# BLDC-PWR-CONROLLER.net
KiCad netlist of a schematic drawn in Altium Designer
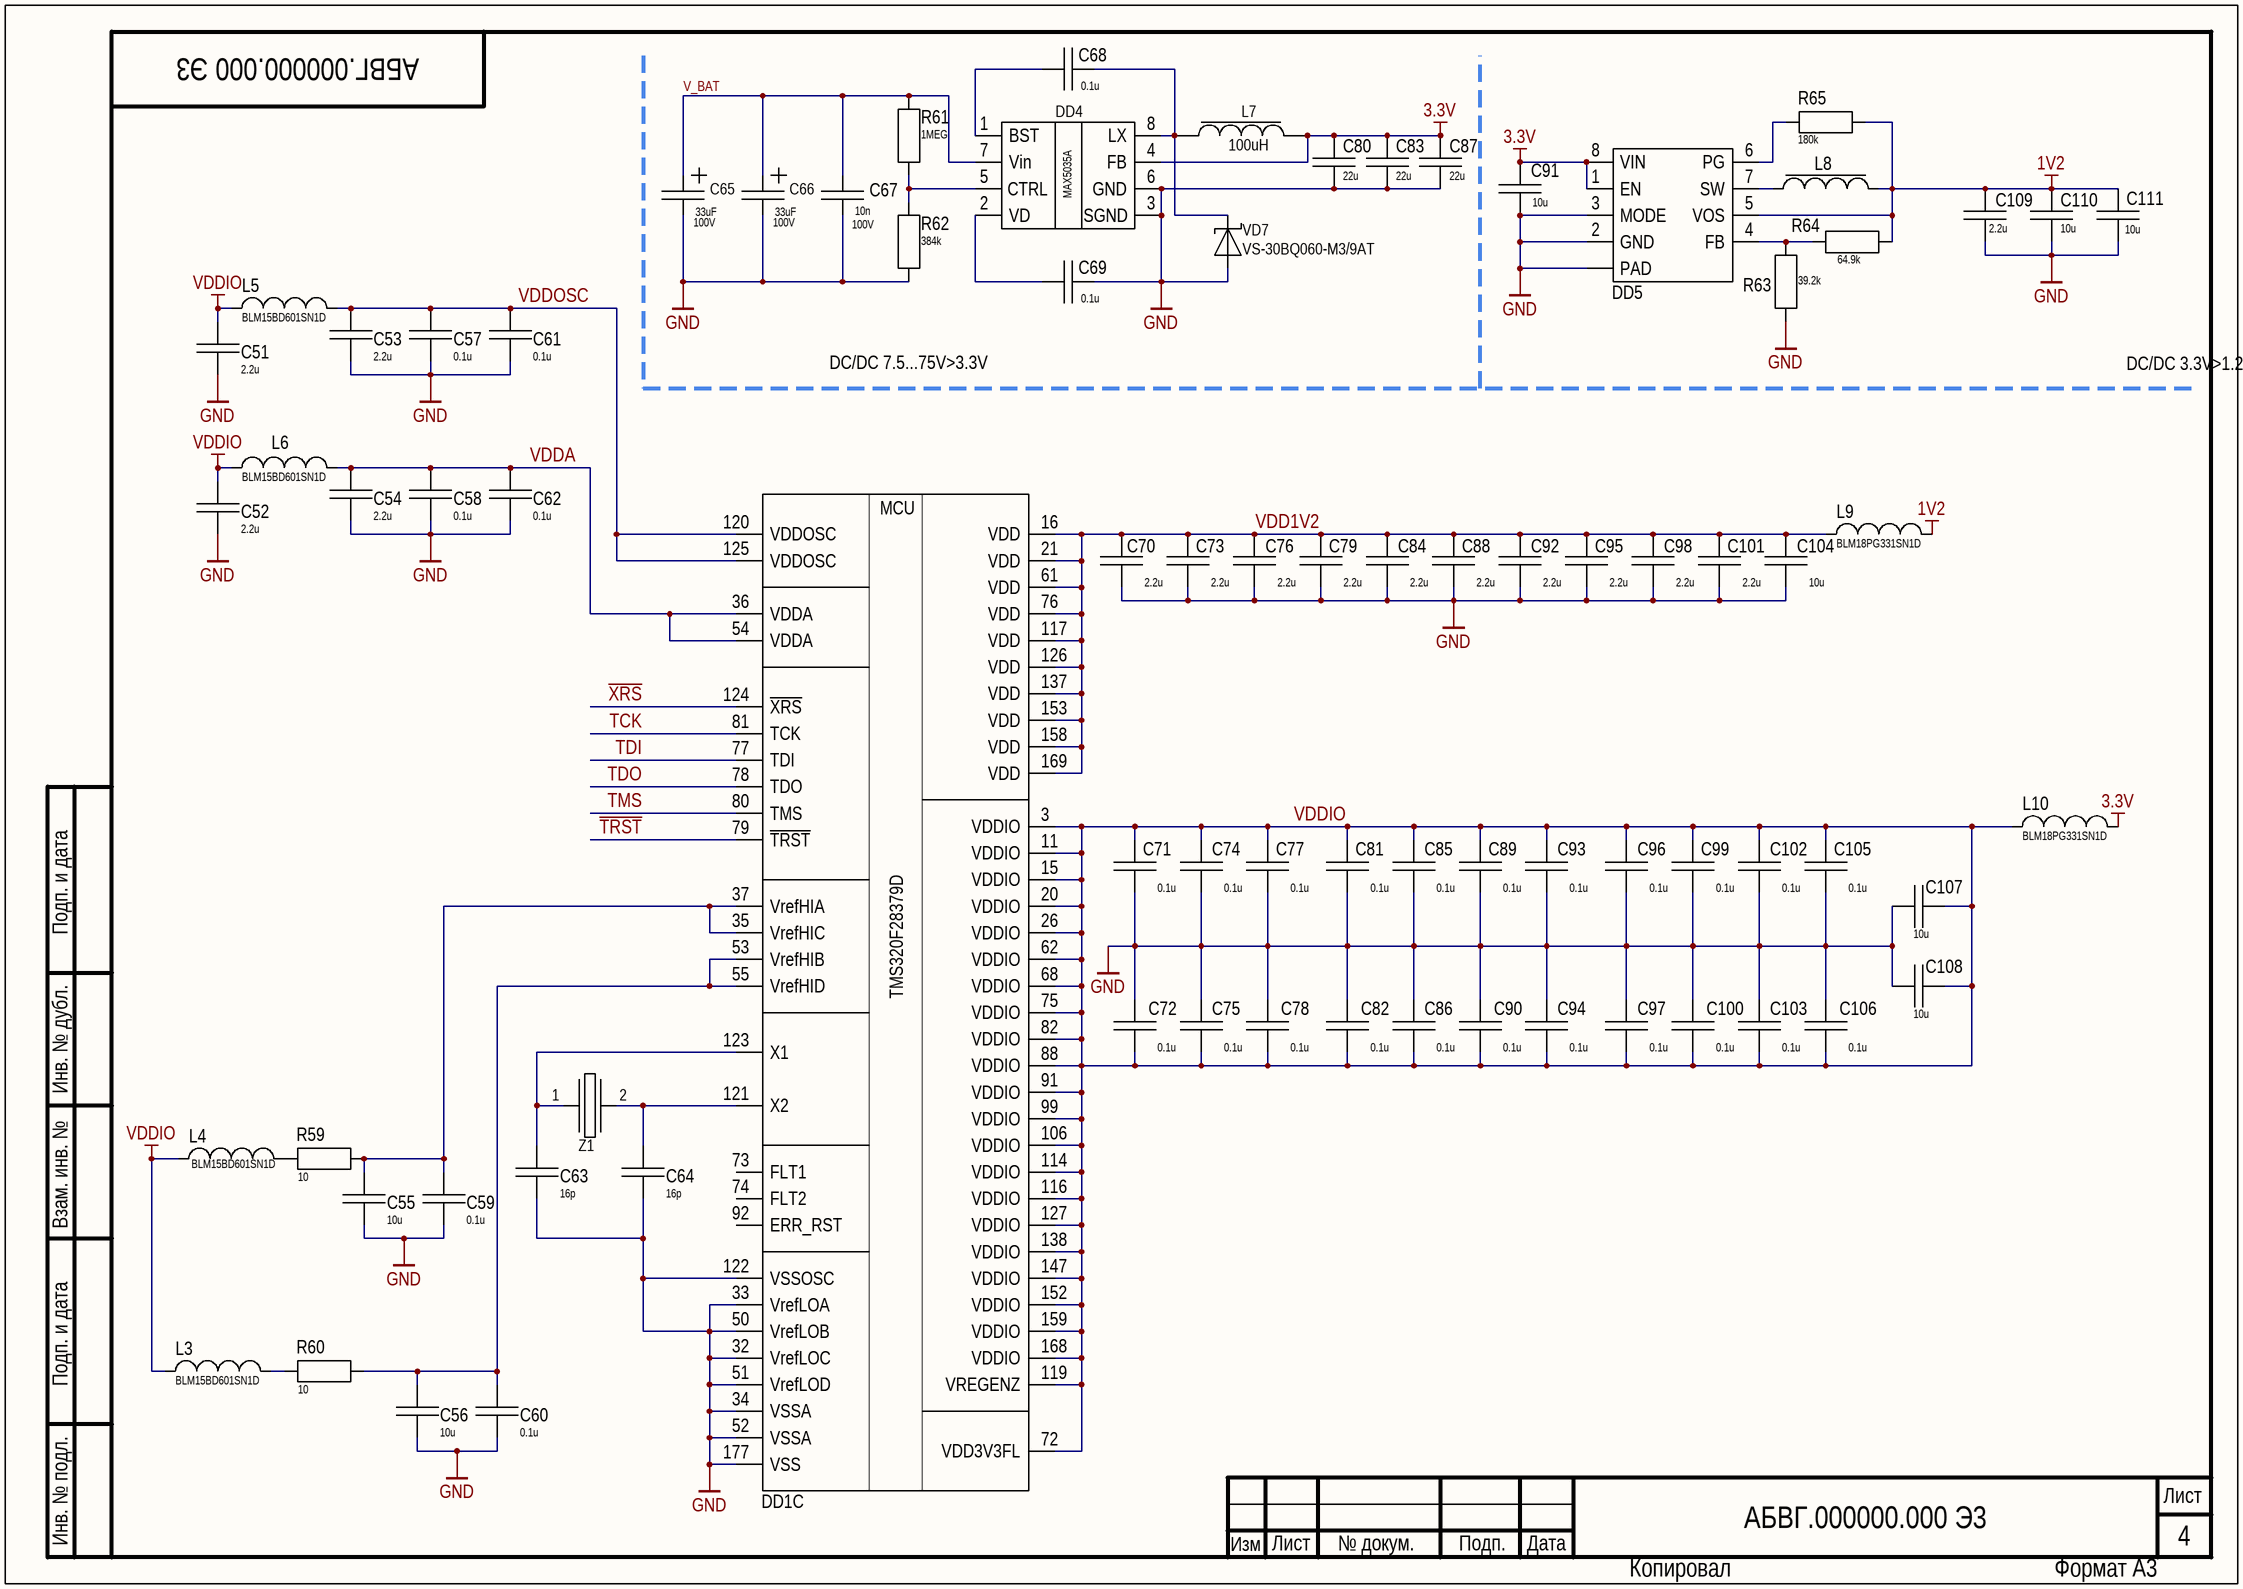
[diagram p0: BLDC-PWR-CONROLLER.SchDoc]

(export (version "E")
  (design (tool "Eeschema 10.0.6"))
  (components
    (comp (ref "C51")
      (value "2.2u")
      (footprint "CAP: 0402")
      (fields (field (name "VOLTAGE") "6.3V") (field (name "PARTNUMBER") "CC0402MRX5R5BB106"))
      (libsource (lib "Fider_Board_Lib") (part "CAP 0402"))
    )
    (comp (ref "C52")
      (value "2.2u")
      (footprint "CAP: 0402")
      (fields (field (name "VOLTAGE") "6.3V") (field (name "PARTNUMBER") "CC0402MRX5R5BB106"))
      (libsource (lib "Fider_Board_Lib") (part "CAP 0402"))
    )
    (comp (ref "C53")
      (value "2.2u")
      (footprint "CAP: 0402")
      (fields (field (name "VOLTAGE") "6.3V") (field (name "PARTNUMBER") "CC0402MRX5R5BB106"))
      (libsource (lib "Fider_Board_Lib") (part "CAP 0402"))
    )
    (comp (ref "C54")
      (value "2.2u")
      (footprint "CAP: 0402")
      (fields (field (name "VOLTAGE") "6.3V") (field (name "PARTNUMBER") "CC0402MRX5R5BB106"))
      (libsource (lib "Fider_Board_Lib") (part "CAP 0402"))
    )
    (comp (ref "C55")
      (value "10u")
      (footprint "CAP: 0402")
      (fields (field (name "VOLTAGE") "6.3V") (field (name "PARTNUMBER") "CC0402MRX5R5BB106"))
      (libsource (lib "Fider_Board_Lib") (part "CAP 0402"))
    )
    (comp (ref "C56")
      (value "10u")
      (footprint "CAP: 0402")
      (fields (field (name "VOLTAGE") "6.3V") (field (name "PARTNUMBER") "CC0402MRX5R5BB106"))
      (libsource (lib "Fider_Board_Lib") (part "CAP 0402"))
    )
    (comp (ref "C57")
      (value "0.1u")
      (footprint "CAP: 0402")
      (fields
        (field (name "VOLTAGE") "10V")
        (field (name "PARTNUMBER") "C0402C104K8PAC")
        (field (name "MANUFACTURER") "Kemet")
      )
      (libsource (lib "Fider_Board_Lib") (part "CAP 0402"))
    )
    (comp (ref "C58")
      (value "0.1u")
      (footprint "CAP: 0402")
      (fields
        (field (name "VOLTAGE") "10V")
        (field (name "PARTNUMBER") "C0402C104K8PAC")
        (field (name "MANUFACTURER") "Kemet")
      )
      (libsource (lib "Fider_Board_Lib") (part "CAP 0402"))
    )
    (comp (ref "C59")
      (value "0.1u")
      (footprint "CAP: 0402")
      (fields
        (field (name "VOLTAGE") "10V")
        (field (name "PARTNUMBER") "C0402C104K8PAC")
        (field (name "MANUFACTURER") "Kemet")
      )
      (libsource (lib "Fider_Board_Lib") (part "CAP 0402"))
    )
    (comp (ref "C60")
      (value "0.1u")
      (footprint "CAP: 0402")
      (fields
        (field (name "VOLTAGE") "10V")
        (field (name "PARTNUMBER") "C0402C104K8PAC")
        (field (name "MANUFACTURER") "Kemet")
      )
      (libsource (lib "Fider_Board_Lib") (part "CAP 0402"))
    )
    (comp (ref "C61")
      (value "0.1u")
      (footprint "CAP: 0402")
      (fields
        (field (name "VOLTAGE") "10V")
        (field (name "PARTNUMBER") "C0402C104K8PAC")
        (field (name "MANUFACTURER") "Kemet")
      )
      (libsource (lib "Fider_Board_Lib") (part "CAP 0402"))
    )
    (comp (ref "C62")
      (value "0.1u")
      (footprint "CAP: 0402")
      (fields
        (field (name "VOLTAGE") "10V")
        (field (name "PARTNUMBER") "C0402C104K8PAC")
        (field (name "MANUFACTURER") "Kemet")
      )
      (libsource (lib "Fider_Board_Lib") (part "CAP 0402"))
    )
    (comp (ref "C63")
      (value "16p")
      (footprint "CAP: 0402")
      (fields
        (field (name "VOLTAGE") "50V")
        (field (name "PARTNUMBER") "GRM1555C1H160JA01D")
        (field (name "MANUFACTURER") "Kemet")
      )
      (libsource (lib "Fider_Board_Lib") (part "CAP 0402"))
    )
    (comp (ref "C64")
      (value "16p")
      (footprint "CAP: 0402")
      (fields
        (field (name "VOLTAGE") "50V")
        (field (name "PARTNUMBER") "GRM1555C1H160JA01D")
        (field (name "MANUFACTURER") "Kemet")
      )
      (libsource (lib "Fider_Board_Lib") (part "CAP 0402"))
    )
    (comp (ref "C65")
      (value "33uF")
      (footprint "ECR08")
      (description "ECR0812")
      (fields (field (name "PARTNUMBER") "JRB2A330M03500800120000B") (field (name "VOLTAGE") "100V"))
      (libsource (lib "capacitors") (part "ECR0812"))
    )
    (comp (ref "C66")
      (value "33uF")
      (footprint "ECR08")
      (description "ECR0812")
      (fields (field (name "PARTNUMBER") "JRB2A330M03500800120000B") (field (name "VOLTAGE") "100V"))
      (libsource (lib "capacitors") (part "ECR0812"))
    )
    (comp (ref "C67")
      (value "10n")
      (footprint "StandardCase:CAP: 0603")
      (fields
        (field (name "MANUFACTURER") "murata")
        (field (name "PARTNUMBER") "GRM188R72A103KA01D")
        (field (name "VALUEMANUFACTURERPARTNUMBER") "Ceramic capacitor, 10n, X7R, ±10%, 100V, 0603, -55...+125°C")
        (field (name "VOLTAGE") "100V")
      )
      (libsource (lib "Capacitor") (part "Ceramic_0603"))
    )
    (comp (ref "C68")
      (value "0.1u")
      (footprint "CAP: 0402")
      (fields
        (field (name "VOLTAGE") "100V")
        (field (name "MANUFACTURER") "Kemet")
        (field (name "TOLERANCE") "10%")
      )
      (libsource (lib "Fider_Board_Lib") (part "CAP 0402"))
    )
    (comp (ref "C69")
      (value "0.1u")
      (footprint "CAP: 0402")
      (fields
        (field (name "VOLTAGE") "100V")
        (field (name "MANUFACTURER") "Kemet")
        (field (name "TOLERANCE") "10%")
      )
      (libsource (lib "Fider_Board_Lib") (part "CAP 0402"))
    )
    (comp (ref "C70")
      (value "2.2u")
      (footprint "CAP: 0402")
      (fields (field (name "VOLTAGE") "6.3V") (field (name "PARTNUMBER") "CC0402MRX5R5BB106"))
      (libsource (lib "Fider_Board_Lib") (part "CAP 0402"))
    )
    (comp (ref "C71")
      (value "0.1u")
      (footprint "CAP: 0402")
      (fields
        (field (name "VOLTAGE") "10V")
        (field (name "PARTNUMBER") "C0402C104K8PAC")
        (field (name "MANUFACTURER") "Kemet")
      )
      (libsource (lib "Fider_Board_Lib") (part "CAP 0402"))
    )
    (comp (ref "C72")
      (value "0.1u")
      (footprint "CAP: 0402")
      (fields
        (field (name "VOLTAGE") "10V")
        (field (name "PARTNUMBER") "C0402C104K8PAC")
        (field (name "MANUFACTURER") "Kemet")
      )
      (libsource (lib "Fider_Board_Lib") (part "CAP 0402"))
    )
    (comp (ref "C73")
      (value "2.2u")
      (footprint "CAP: 0402")
      (fields (field (name "VOLTAGE") "6.3V") (field (name "PARTNUMBER") "CC0402MRX5R5BB106"))
      (libsource (lib "Fider_Board_Lib") (part "CAP 0402"))
    )
    (comp (ref "C74")
      (value "0.1u")
      (footprint "CAP: 0402")
      (fields
        (field (name "VOLTAGE") "10V")
        (field (name "PARTNUMBER") "C0402C104K8PAC")
        (field (name "MANUFACTURER") "Kemet")
      )
      (libsource (lib "Fider_Board_Lib") (part "CAP 0402"))
    )
    (comp (ref "C75")
      (value "0.1u")
      (footprint "CAP: 0402")
      (fields
        (field (name "VOLTAGE") "10V")
        (field (name "PARTNUMBER") "C0402C104K8PAC")
        (field (name "MANUFACTURER") "Kemet")
      )
      (libsource (lib "Fider_Board_Lib") (part "CAP 0402"))
    )
    (comp (ref "C76")
      (value "2.2u")
      (footprint "CAP: 0402")
      (fields (field (name "VOLTAGE") "6.3V") (field (name "PARTNUMBER") "CC0402MRX5R5BB106"))
      (libsource (lib "Fider_Board_Lib") (part "CAP 0402"))
    )
    (comp (ref "C77")
      (value "0.1u")
      (footprint "CAP: 0402")
      (fields
        (field (name "VOLTAGE") "10V")
        (field (name "PARTNUMBER") "C0402C104K8PAC")
        (field (name "MANUFACTURER") "Kemet")
      )
      (libsource (lib "Fider_Board_Lib") (part "CAP 0402"))
    )
    (comp (ref "C78")
      (value "0.1u")
      (footprint "CAP: 0402")
      (fields
        (field (name "VOLTAGE") "10V")
        (field (name "PARTNUMBER") "C0402C104K8PAC")
        (field (name "MANUFACTURER") "Kemet")
      )
      (libsource (lib "Fider_Board_Lib") (part "CAP 0402"))
    )
    (comp (ref "C79")
      (value "2.2u")
      (footprint "CAP: 0402")
      (fields (field (name "VOLTAGE") "6.3V") (field (name "PARTNUMBER") "CC0402MRX5R5BB106"))
      (libsource (lib "Fider_Board_Lib") (part "CAP 0402"))
    )
    (comp (ref "C80")
      (value "22u")
      (footprint "CAP: 0805")
      (fields (field (name "VOLTAGE") "6.3V") (field (name "PARTNUMBER") "GRM21BR60J226M*"))
      (libsource (lib "Fider_Board_Lib") (part "CAP 0805"))
    )
    (comp (ref "C81")
      (value "0.1u")
      (footprint "CAP: 0402")
      (fields
        (field (name "VOLTAGE") "10V")
        (field (name "PARTNUMBER") "C0402C104K8PAC")
        (field (name "MANUFACTURER") "Kemet")
      )
      (libsource (lib "Fider_Board_Lib") (part "CAP 0402"))
    )
    (comp (ref "C82")
      (value "0.1u")
      (footprint "CAP: 0402")
      (fields
        (field (name "VOLTAGE") "10V")
        (field (name "PARTNUMBER") "C0402C104K8PAC")
        (field (name "MANUFACTURER") "Kemet")
      )
      (libsource (lib "Fider_Board_Lib") (part "CAP 0402"))
    )
    (comp (ref "C83")
      (value "22u")
      (footprint "CAP: 0805")
      (fields (field (name "VOLTAGE") "6.3V") (field (name "PARTNUMBER") "GRM21BR60J226M*"))
      (libsource (lib "Fider_Board_Lib") (part "CAP 0805"))
    )
    (comp (ref "C84")
      (value "2.2u")
      (footprint "CAP: 0402")
      (fields (field (name "VOLTAGE") "6.3V") (field (name "PARTNUMBER") "CC0402MRX5R5BB106"))
      (libsource (lib "Fider_Board_Lib") (part "CAP 0402"))
    )
    (comp (ref "C85")
      (value "0.1u")
      (footprint "CAP: 0402")
      (fields
        (field (name "VOLTAGE") "10V")
        (field (name "PARTNUMBER") "C0402C104K8PAC")
        (field (name "MANUFACTURER") "Kemet")
      )
      (libsource (lib "Fider_Board_Lib") (part "CAP 0402"))
    )
    (comp (ref "C86")
      (value "0.1u")
      (footprint "CAP: 0402")
      (fields
        (field (name "VOLTAGE") "10V")
        (field (name "PARTNUMBER") "C0402C104K8PAC")
        (field (name "MANUFACTURER") "Kemet")
      )
      (libsource (lib "Fider_Board_Lib") (part "CAP 0402"))
    )
    (comp (ref "C87")
      (value "22u")
      (footprint "CAP: 0805")
      (fields (field (name "VOLTAGE") "6.3V") (field (name "PARTNUMBER") "GRM21BR60J226M*"))
      (libsource (lib "Fider_Board_Lib") (part "CAP 0805"))
    )
    (comp (ref "C88")
      (value "2.2u")
      (footprint "CAP: 0402")
      (fields (field (name "VOLTAGE") "6.3V") (field (name "PARTNUMBER") "CC0402MRX5R5BB106"))
      (libsource (lib "Fider_Board_Lib") (part "CAP 0402"))
    )
    (comp (ref "C89")
      (value "0.1u")
      (footprint "CAP: 0402")
      (fields
        (field (name "VOLTAGE") "10V")
        (field (name "PARTNUMBER") "C0402C104K8PAC")
        (field (name "MANUFACTURER") "Kemet")
      )
      (libsource (lib "Fider_Board_Lib") (part "CAP 0402"))
    )
    (comp (ref "C90")
      (value "0.1u")
      (footprint "CAP: 0402")
      (fields
        (field (name "VOLTAGE") "10V")
        (field (name "PARTNUMBER") "C0402C104K8PAC")
        (field (name "MANUFACTURER") "Kemet")
      )
      (libsource (lib "Fider_Board_Lib") (part "CAP 0402"))
    )
    (comp (ref "C91")
      (value "10u")
      (footprint "CAP: 0805")
      (fields (field (name "VOLTAGE") "6.3V") (field (name "PARTNUMBER") "CC0402MRX5R5BB106"))
      (libsource (lib "Fider_Board_Lib") (part "CAP 0805"))
    )
    (comp (ref "C92")
      (value "2.2u")
      (footprint "CAP: 0402")
      (fields (field (name "VOLTAGE") "6.3V") (field (name "PARTNUMBER") "CC0402MRX5R5BB106"))
      (libsource (lib "Fider_Board_Lib") (part "CAP 0402"))
    )
    (comp (ref "C93")
      (value "0.1u")
      (footprint "CAP: 0402")
      (fields
        (field (name "VOLTAGE") "10V")
        (field (name "PARTNUMBER") "C0402C104K8PAC")
        (field (name "MANUFACTURER") "Kemet")
      )
      (libsource (lib "Fider_Board_Lib") (part "CAP 0402"))
    )
    (comp (ref "C94")
      (value "0.1u")
      (footprint "CAP: 0402")
      (fields
        (field (name "VOLTAGE") "10V")
        (field (name "PARTNUMBER") "C0402C104K8PAC")
        (field (name "MANUFACTURER") "Kemet")
      )
      (libsource (lib "Fider_Board_Lib") (part "CAP 0402"))
    )
    (comp (ref "C95")
      (value "2.2u")
      (footprint "CAP: 0402")
      (fields (field (name "VOLTAGE") "6.3V") (field (name "PARTNUMBER") "CC0402MRX5R5BB106"))
      (libsource (lib "Fider_Board_Lib") (part "CAP 0402"))
    )
    (comp (ref "C96")
      (value "0.1u")
      (footprint "CAP: 0402")
      (fields
        (field (name "VOLTAGE") "10V")
        (field (name "PARTNUMBER") "C0402C104K8PAC")
        (field (name "MANUFACTURER") "Kemet")
      )
      (libsource (lib "Fider_Board_Lib") (part "CAP 0402"))
    )
    (comp (ref "C97")
      (value "0.1u")
      (footprint "CAP: 0402")
      (fields
        (field (name "VOLTAGE") "10V")
        (field (name "PARTNUMBER") "C0402C104K8PAC")
        (field (name "MANUFACTURER") "Kemet")
      )
      (libsource (lib "Fider_Board_Lib") (part "CAP 0402"))
    )
    (comp (ref "C98")
      (value "2.2u")
      (footprint "CAP: 0402")
      (fields (field (name "VOLTAGE") "6.3V") (field (name "PARTNUMBER") "CC0402MRX5R5BB106"))
      (libsource (lib "Fider_Board_Lib") (part "CAP 0402"))
    )
    (comp (ref "C99")
      (value "0.1u")
      (footprint "CAP: 0402")
      (fields
        (field (name "VOLTAGE") "10V")
        (field (name "PARTNUMBER") "C0402C104K8PAC")
        (field (name "MANUFACTURER") "Kemet")
      )
      (libsource (lib "Fider_Board_Lib") (part "CAP 0402"))
    )
    (comp (ref "C100")
      (value "0.1u")
      (footprint "CAP: 0402")
      (fields
        (field (name "VOLTAGE") "10V")
        (field (name "PARTNUMBER") "C0402C104K8PAC")
        (field (name "MANUFACTURER") "Kemet")
      )
      (libsource (lib "Fider_Board_Lib") (part "CAP 0402"))
    )
    (comp (ref "C101")
      (value "2.2u")
      (footprint "CAP: 0402")
      (fields (field (name "VOLTAGE") "6.3V") (field (name "PARTNUMBER") "CC0402MRX5R5BB106"))
      (libsource (lib "Fider_Board_Lib") (part "CAP 0402"))
    )
    (comp (ref "C102")
      (value "0.1u")
      (footprint "CAP: 0402")
      (fields
        (field (name "VOLTAGE") "10V")
        (field (name "PARTNUMBER") "C0402C104K8PAC")
        (field (name "MANUFACTURER") "Kemet")
      )
      (libsource (lib "Fider_Board_Lib") (part "CAP 0402"))
    )
    (comp (ref "C103")
      (value "0.1u")
      (footprint "CAP: 0402")
      (fields
        (field (name "VOLTAGE") "10V")
        (field (name "PARTNUMBER") "C0402C104K8PAC")
        (field (name "MANUFACTURER") "Kemet")
      )
      (libsource (lib "Fider_Board_Lib") (part "CAP 0402"))
    )
    (comp (ref "C104")
      (value "10u")
      (footprint "CAP: 0402")
      (fields (field (name "VOLTAGE") "6.3V") (field (name "PARTNUMBER") "CC0402MRX5R5BB106"))
      (libsource (lib "Fider_Board_Lib") (part "CAP 0402"))
    )
    (comp (ref "C105")
      (value "0.1u")
      (footprint "CAP: 0402")
      (fields
        (field (name "VOLTAGE") "10V")
        (field (name "PARTNUMBER") "C0402C104K8PAC")
        (field (name "MANUFACTURER") "Kemet")
      )
      (libsource (lib "Fider_Board_Lib") (part "CAP 0402"))
    )
    (comp (ref "C106")
      (value "0.1u")
      (footprint "CAP: 0402")
      (fields
        (field (name "VOLTAGE") "10V")
        (field (name "PARTNUMBER") "C0402C104K8PAC")
        (field (name "MANUFACTURER") "Kemet")
      )
      (libsource (lib "Fider_Board_Lib") (part "CAP 0402"))
    )
    (comp (ref "C107")
      (value "10u")
      (footprint "CAP: 0402")
      (fields (field (name "VOLTAGE") "6.3V") (field (name "PARTNUMBER") "CC0402MRX5R5BB106"))
      (libsource (lib "Fider_Board_Lib") (part "CAP 0402"))
    )
    (comp (ref "C108")
      (value "10u")
      (footprint "CAP: 0402")
      (fields (field (name "VOLTAGE") "6.3V") (field (name "PARTNUMBER") "CC0402MRX5R5BB106"))
      (libsource (lib "Fider_Board_Lib") (part "CAP 0402"))
    )
    (comp (ref "C109")
      (value "2.2u")
      (footprint "CAP: 0402")
      (fields (field (name "VOLTAGE") "6.3V") (field (name "PARTNUMBER") "CC0402MRX5R5BB106"))
      (libsource (lib "Fider_Board_Lib") (part "CAP 0402"))
    )
    (comp (ref "C110")
      (value "10u")
      (footprint "CAP: 0805")
      (fields (field (name "VOLTAGE") "6.3V") (field (name "PARTNUMBER") "CC0402MRX5R5BB106"))
      (libsource (lib "Fider_Board_Lib") (part "CAP 0805"))
    )
    (comp (ref "C111")
      (value "10u")
      (footprint "CAP: 0805")
      (fields (field (name "VOLTAGE") "6.3V") (field (name "PARTNUMBER") "CC0402MRX5R5BB106"))
      (libsource (lib "Fider_Board_Lib") (part "CAP 0805"))
    )
    (comp (ref "DD1")
      (value "TMS320F28379DPTP_LACID")
      (footprint "176-HLQFP")
      (fields (field (name "PARTNUMBER") "TMS320F28379DPTPT"))
      (libsource (lib "BKM_SCH_Lib") (part "TMS320F28379DPTP_LACID"))
    )
    (comp (ref "DD4")
      (value "MAX5035A")
      (footprint "SOIC-8-150-1.27")
      (libsource (lib "BKM_SCH_Lib") (part "MAX5035*"))
    )
    (comp (ref "DD5")
      (value "TPS62080ADSGT")
      (footprint "8-WSON 2.1x2.1")
      (fields (field (name "PARTNUMBER") "TPS61023DRLR"))
      (libsource (lib "BKM_SCH_Lib") (part "TPS62080ADSGT"))
    )
    (comp (ref "L3")
      (value "BLM15BD601SN1D")
      (footprint "IND: 0402")
      (libsource (lib "Fider_Board_Lib") (part "BLM15BD601SN1D"))
    )
    (comp (ref "L4")
      (value "BLM15BD601SN1D")
      (footprint "IND: 0402")
      (libsource (lib "Fider_Board_Lib") (part "BLM15BD601SN1D"))
    )
    (comp (ref "L5")
      (value "BLM15BD601SN1D")
      (footprint "IND: 0402")
      (libsource (lib "Fider_Board_Lib") (part "BLM15BD601SN1D"))
    )
    (comp (ref "L6")
      (value "BLM15BD601SN1D")
      (footprint "IND: 0402")
      (libsource (lib "Fider_Board_Lib") (part "BLM15BD601SN1D"))
    )
    (comp (ref "L7")
      (value "100uH")
      (footprint "CustomCase:IND: SRR1208")
      (fields
        (field (name "MANUFACTURER") "EPCOS")
        (field (name "PARTNUMBER") "B82477G4104M000")
        (field (name "TOLERANCE") "20%")
      )
      (libsource (lib "Inductor") (part "Inductor_SRR1208"))
    )
    (comp (ref "L8")
      (value "LQH3NPN")
      (footprint "IND: LQH3NP")
      (fields (field (name "PARTNUMBER") "LQH3NPN1R0NJ0L"))
      (libsource (lib "BKM_SCH_Lib") (part "LQH3NPN"))
    )
    (comp (ref "L9")
      (value "BLM18PG331SN1D")
      (footprint "IND: 0603")
      (libsource (lib "Fider_Board_Lib") (part "BLM18PG331SN1D"))
    )
    (comp (ref "L10")
      (value "BLM18PG331SN1D")
      (footprint "IND: 0603")
      (libsource (lib "Fider_Board_Lib") (part "BLM18PG331SN1D"))
    )
    (comp (ref "R59")
      (value "10")
      (footprint "RES: 0402")
      (fields (field (name "PARTNUMBER") "RC0402FR-071KL") (field (name "TOLERANCE") "1%"))
      (libsource (lib "Fider_Board_Lib") (part "RES 0402"))
    )
    (comp (ref "R60")
      (value "10")
      (footprint "RES: 0402")
      (fields (field (name "PARTNUMBER") "RC0402FR-071KL") (field (name "TOLERANCE") "1%"))
      (libsource (lib "Fider_Board_Lib") (part "RES 0402"))
    )
    (comp (ref "R61")
      (value "1MEG")
      (footprint "RES: 0402")
      (fields (field (name "PARTNUMBER") "RC0402FR-1339K2L") (field (name "TOLERANCE") "1%"))
      (libsource (lib "Fider_Board_Lib") (part "RES 0402"))
    )
    (comp (ref "R62")
      (value "384k")
      (footprint "RES: 0402")
      (fields (field (name "PARTNUMBER") "RC0402FR-1339K2L") (field (name "TOLERANCE") "1%"))
      (libsource (lib "Fider_Board_Lib") (part "RES 0402"))
    )
    (comp (ref "R63")
      (value "39.2k")
      (footprint "RES: 0402")
      (fields (field (name "PARTNUMBER") "RC0402FR-1339K2L") (field (name "TOLERANCE") "1%"))
      (libsource (lib "Fider_Board_Lib") (part "RES 0402"))
    )
    (comp (ref "R64")
      (value "64.9k")
      (footprint "RES: 0402")
      (fields (field (name "PARTNUMBER") "RC0402FR-1364K9L") (field (name "TOLERANCE") "1%"))
      (libsource (lib "Fider_Board_Lib") (part "RES 0402"))
    )
    (comp (ref "R65")
      (value "180k")
      (footprint "RES: 0402")
      (fields (field (name "PARTNUMBER") "RC0402FR-07180RL") (field (name "TOLERANCE") "1%"))
      (libsource (lib "Fider_Board_Lib") (part "RES 0402"))
    )
    (comp (ref "VD7")
      (value "~")
      (footprint "StandardCase:DIODE: SMC")
      (fields
        (field (name "MANUFACTURER") "Diodes Incorporated")
        (field (name "VALUEMANUFACTURERPARTNUMBER") "Schottky diode, 80V, 500mA, 1V, 15pF, SOD-123, -55...+150°C")
        (field (name "VOLTAGE") "80V")
        (field (name "PARTNUMBER") "VS-30BQ060-M3/9AT")
      )
      (libsource (lib "Diode") (part "Schottky_single"))
    )
    (comp (ref "Z1")
      (value "~")
      (footprint "CustomCase:OSC: HC49SM")
      (fields
        (field (name "MANUFACTURER") "Epson")
        (field (name "PARTNUMBER") "FC-135 32.7680KA-A5")
        (field (name "VALUEMANUFACTURERPARTNUMBER") "Crystal, , 12.5pF, ±20ppm, case 3215, -40...+85°C")
      )
      (libsource (lib "Oscilator") (part "Crystal_HC-49SM"))
    )
  )
  (nets
    (net (code "1") (name "/TCK") (class "Default")
      (node (ref "DD1") (pin "81") (pinfunction "TCK_81") (pintype "power_in"))
    )
    (net (code "2") (name "/TDI") (class "Default")
      (node (ref "DD1") (pin "77") (pinfunction "TDI_77") (pintype "power_in"))
    )
    (net (code "3") (name "/TDO") (class "Default")
      (node (ref "DD1") (pin "78") (pinfunction "TDO_78") (pintype "power_in"))
    )
    (net (code "4") (name "/TMS") (class "Default")
      (node (ref "DD1") (pin "80") (pinfunction "TMS_80") (pintype "power_in"))
    )
    (net (code "5") (name "/VDD1V2") (class "Default")
      (node (ref "C101") (pin "2") (pinfunction "2_2") (pintype "passive"))
      (node (ref "C104") (pin "2") (pinfunction "2_2") (pintype "passive"))
      (node (ref "C70") (pin "2") (pinfunction "2_2") (pintype "passive"))
      (node (ref "C73") (pin "2") (pinfunction "2_2") (pintype "passive"))
      (node (ref "C76") (pin "2") (pinfunction "2_2") (pintype "passive"))
      (node (ref "C79") (pin "2") (pinfunction "2_2") (pintype "passive"))
      (node (ref "C84") (pin "2") (pinfunction "2_2") (pintype "passive"))
      (node (ref "C88") (pin "2") (pinfunction "2_2") (pintype "passive"))
      (node (ref "C92") (pin "2") (pinfunction "2_2") (pintype "passive"))
      (node (ref "C95") (pin "2") (pinfunction "2_2") (pintype "passive"))
      (node (ref "C98") (pin "2") (pinfunction "2_2") (pintype "passive"))
      (node (ref "DD1") (pin "117") (pinfunction "VDD_117") (pintype "power_in"))
      (node (ref "DD1") (pin "126") (pinfunction "VDD_126") (pintype "power_in"))
      (node (ref "DD1") (pin "137") (pinfunction "VDD_137") (pintype "power_in"))
      (node (ref "DD1") (pin "153") (pinfunction "VDD_153") (pintype "power_in"))
      (node (ref "DD1") (pin "158") (pinfunction "VDD_158") (pintype "power_in"))
      (node (ref "DD1") (pin "16") (pinfunction "VDD_16") (pintype "power_in"))
      (node (ref "DD1") (pin "169") (pinfunction "VDD_169") (pintype "power_in"))
      (node (ref "DD1") (pin "21") (pinfunction "VDD_21") (pintype "power_in"))
      (node (ref "DD1") (pin "61") (pinfunction "VDD_61") (pintype "power_in"))
      (node (ref "DD1") (pin "76") (pinfunction "VDD_76") (pintype "power_in"))
      (node (ref "L9") (pin "1") (pinfunction "1_1") (pintype "passive"))
    )
    (net (code "6") (name "/VDDA") (class "Default")
      (node (ref "C54") (pin "2") (pinfunction "2_2") (pintype "passive"))
      (node (ref "C58") (pin "2") (pinfunction "2_2") (pintype "passive"))
      (node (ref "C62") (pin "2") (pinfunction "2_2") (pintype "passive"))
      (node (ref "DD1") (pin "36") (pinfunction "VDDA_36") (pintype "power_in"))
      (node (ref "DD1") (pin "54") (pinfunction "VDDA_54") (pintype "power_in"))
      (node (ref "L6") (pin "2") (pinfunction "2_2") (pintype "passive"))
    )
    (net (code "7") (name "/VDDOSC") (class "Default")
      (node (ref "C53") (pin "2") (pinfunction "2_2") (pintype "passive"))
      (node (ref "C57") (pin "2") (pinfunction "2_2") (pintype "passive"))
      (node (ref "C61") (pin "2") (pinfunction "2_2") (pintype "passive"))
      (node (ref "DD1") (pin "120") (pinfunction "VDDOSC_120") (pintype "power_in"))
      (node (ref "DD1") (pin "125") (pinfunction "VDDOSC_125") (pintype "power_in"))
      (node (ref "L5") (pin "2") (pinfunction "2_2") (pintype "passive"))
    )
    (net (code "8") (name "/V_BAT") (class "Default")
      (node (ref "C65") (pin "1") (pinfunction "1_1") (pintype "passive"))
      (node (ref "C66") (pin "1") (pinfunction "1_1") (pintype "passive"))
      (node (ref "C67") (pin "2") (pinfunction "2_2") (pintype "power_in"))
      (node (ref "DD4") (pin "7") (pinfunction "Vin_7") (pintype "passive"))
      (node (ref "R61") (pin "2") (pinfunction "2_2") (pintype "passive"))
    )
    (net (code "9") (name "/~{TRST}") (class "Default")
      (node (ref "DD1") (pin "79") (pinfunction "~{TRST}_79") (pintype "power_in"))
    )
    (net (code "10") (name "/~{XRS}") (class "Default")
      (node (ref "DD1") (pin "124") (pinfunction "~{XRS}_124") (pintype "power_in"))
    )
    (net (code "11") (name "1V2") (class "Default")
      (node (ref "C109") (pin "2") (pinfunction "2_2") (pintype "passive"))
      (node (ref "C110") (pin "2") (pinfunction "2_2") (pintype "passive"))
      (node (ref "C111") (pin "2") (pinfunction "2_2") (pintype "passive"))
      (node (ref "DD5") (pin "5") (pinfunction "VOS_5") (pintype "passive"))
      (node (ref "L8") (pin "1") (pinfunction "1_1") (pintype "passive"))
      (node (ref "L9") (pin "2") (pinfunction "2_2") (pintype "passive"))
      (node (ref "R64") (pin "1") (pinfunction "1_1") (pintype "passive"))
      (node (ref "R65") (pin "1") (pinfunction "1_1") (pintype "passive"))
    )
    (net (code "12") (name "3.3V") (class "Default")
      (node (ref "C80") (pin "2") (pinfunction "2_2") (pintype "passive"))
      (node (ref "C83") (pin "2") (pinfunction "2_2") (pintype "passive"))
      (node (ref "C87") (pin "2") (pinfunction "2_2") (pintype "passive"))
      (node (ref "C91") (pin "2") (pinfunction "2_2") (pintype "passive"))
      (node (ref "DD4") (pin "4") (pinfunction "FB_4") (pintype "passive"))
      (node (ref "DD5") (pin "1") (pinfunction "EN_1") (pintype "passive"))
      (node (ref "DD5") (pin "8") (pinfunction "VIN_8") (pintype "passive"))
      (node (ref "L10") (pin "2") (pinfunction "2_2") (pintype "passive"))
      (node (ref "L7") (pin "1") (pinfunction "1_1") (pintype "passive"))
    )
    (net (code "13") (name "GND") (class "Default")
      (node (ref "C100") (pin "2") (pinfunction "2_2") (pintype "passive"))
      (node (ref "C101") (pin "1") (pinfunction "1_1") (pintype "passive"))
      (node (ref "C102") (pin "1") (pinfunction "1_1") (pintype "passive"))
      (node (ref "C103") (pin "2") (pinfunction "2_2") (pintype "passive"))
      (node (ref "C104") (pin "1") (pinfunction "1_1") (pintype "passive"))
      (node (ref "C105") (pin "1") (pinfunction "1_1") (pintype "passive"))
      (node (ref "C106") (pin "2") (pinfunction "2_2") (pintype "passive"))
      (node (ref "C107") (pin "2") (pinfunction "2_2") (pintype "passive"))
      (node (ref "C108") (pin "2") (pinfunction "2_2") (pintype "passive"))
      (node (ref "C109") (pin "1") (pinfunction "1_1") (pintype "passive"))
      (node (ref "C110") (pin "1") (pinfunction "1_1") (pintype "passive"))
      (node (ref "C111") (pin "1") (pinfunction "1_1") (pintype "passive"))
      (node (ref "C51") (pin "1") (pinfunction "1_1") (pintype "passive"))
      (node (ref "C52") (pin "1") (pinfunction "1_1") (pintype "passive"))
      (node (ref "C53") (pin "1") (pinfunction "1_1") (pintype "passive"))
      (node (ref "C54") (pin "1") (pinfunction "1_1") (pintype "passive"))
      (node (ref "C55") (pin "1") (pinfunction "1_1") (pintype "passive"))
      (node (ref "C56") (pin "1") (pinfunction "1_1") (pintype "passive"))
      (node (ref "C57") (pin "1") (pinfunction "1_1") (pintype "passive"))
      (node (ref "C58") (pin "1") (pinfunction "1_1") (pintype "passive"))
      (node (ref "C59") (pin "1") (pinfunction "1_1") (pintype "passive"))
      (node (ref "C60") (pin "1") (pinfunction "1_1") (pintype "passive"))
      (node (ref "C61") (pin "1") (pinfunction "1_1") (pintype "passive"))
      (node (ref "C62") (pin "1") (pinfunction "1_1") (pintype "passive"))
      (node (ref "C63") (pin "1") (pinfunction "1_1") (pintype "passive"))
      (node (ref "C64") (pin "1") (pinfunction "1_1") (pintype "passive"))
      (node (ref "C65") (pin "2") (pinfunction "2_2") (pintype "passive"))
      (node (ref "C66") (pin "2") (pinfunction "2_2") (pintype "passive"))
      (node (ref "C67") (pin "1") (pinfunction "1_1") (pintype "power_in"))
      (node (ref "C69") (pin "1") (pinfunction "1_1") (pintype "passive"))
      (node (ref "C70") (pin "1") (pinfunction "1_1") (pintype "passive"))
      (node (ref "C71") (pin "1") (pinfunction "1_1") (pintype "passive"))
      (node (ref "C72") (pin "2") (pinfunction "2_2") (pintype "passive"))
      (node (ref "C73") (pin "1") (pinfunction "1_1") (pintype "passive"))
      (node (ref "C74") (pin "1") (pinfunction "1_1") (pintype "passive"))
      (node (ref "C75") (pin "2") (pinfunction "2_2") (pintype "passive"))
      (node (ref "C76") (pin "1") (pinfunction "1_1") (pintype "passive"))
      (node (ref "C77") (pin "1") (pinfunction "1_1") (pintype "passive"))
      (node (ref "C78") (pin "2") (pinfunction "2_2") (pintype "passive"))
      (node (ref "C79") (pin "1") (pinfunction "1_1") (pintype "passive"))
      (node (ref "C80") (pin "1") (pinfunction "1_1") (pintype "passive"))
      (node (ref "C81") (pin "1") (pinfunction "1_1") (pintype "passive"))
      (node (ref "C82") (pin "2") (pinfunction "2_2") (pintype "passive"))
      (node (ref "C83") (pin "1") (pinfunction "1_1") (pintype "passive"))
      (node (ref "C84") (pin "1") (pinfunction "1_1") (pintype "passive"))
      (node (ref "C85") (pin "1") (pinfunction "1_1") (pintype "passive"))
      (node (ref "C86") (pin "2") (pinfunction "2_2") (pintype "passive"))
      (node (ref "C87") (pin "1") (pinfunction "1_1") (pintype "passive"))
      (node (ref "C88") (pin "1") (pinfunction "1_1") (pintype "passive"))
      (node (ref "C89") (pin "1") (pinfunction "1_1") (pintype "passive"))
      (node (ref "C90") (pin "2") (pinfunction "2_2") (pintype "passive"))
      (node (ref "C91") (pin "1") (pinfunction "1_1") (pintype "passive"))
      (node (ref "C92") (pin "1") (pinfunction "1_1") (pintype "passive"))
      (node (ref "C93") (pin "1") (pinfunction "1_1") (pintype "passive"))
      (node (ref "C94") (pin "2") (pinfunction "2_2") (pintype "passive"))
      (node (ref "C95") (pin "1") (pinfunction "1_1") (pintype "passive"))
      (node (ref "C96") (pin "1") (pinfunction "1_1") (pintype "passive"))
      (node (ref "C97") (pin "2") (pinfunction "2_2") (pintype "passive"))
      (node (ref "C98") (pin "1") (pinfunction "1_1") (pintype "passive"))
      (node (ref "C99") (pin "1") (pinfunction "1_1") (pintype "passive"))
      (node (ref "DD1") (pin "122") (pinfunction "VSSOSC_122") (pintype "passive"))
      (node (ref "DD1") (pin "177") (pinfunction "VSS_177") (pintype "power_in"))
      (node (ref "DD1") (pin "32") (pinfunction "VrefLOC_32") (pintype "power_in"))
      (node (ref "DD1") (pin "33") (pinfunction "VrefLOA_33") (pintype "power_in"))
      (node (ref "DD1") (pin "34") (pinfunction "VSSA_34") (pintype "power_in"))
      (node (ref "DD1") (pin "50") (pinfunction "VrefLOB_50") (pintype "power_in"))
      (node (ref "DD1") (pin "51") (pinfunction "VrefLOD_51") (pintype "power_in"))
      (node (ref "DD1") (pin "52") (pinfunction "VSSA_52") (pintype "power_in"))
      (node (ref "DD4") (pin "3") (pinfunction "SGND_3") (pintype "passive"))
      (node (ref "DD4") (pin "6") (pinfunction "GND_6") (pintype "passive"))
      (node (ref "DD5") (pin "0") (pinfunction "PAD_0") (pintype "passive"))
      (node (ref "DD5") (pin "2") (pinfunction "GND_2") (pintype "passive"))
      (node (ref "DD5") (pin "3") (pinfunction "MODE_3") (pintype "passive"))
      (node (ref "R62") (pin "1") (pinfunction "1_1") (pintype "passive"))
      (node (ref "R63") (pin "1") (pinfunction "1_1") (pintype "passive"))
      (node (ref "VD7") (pin "1") (pinfunction "1_1") (pintype "passive"))
    )
    (net (code "14") (name "Net-(DD1C-VrefHIA)") (class "Default")
      (node (ref "C55") (pin "2") (pinfunction "2_2") (pintype "passive"))
      (node (ref "C59") (pin "2") (pinfunction "2_2") (pintype "passive"))
      (node (ref "DD1") (pin "35") (pinfunction "VrefHIC_35") (pintype "power_in"))
      (node (ref "DD1") (pin "37") (pinfunction "VrefHIA_37") (pintype "power_in"))
      (node (ref "R59") (pin "1") (pinfunction "1_1") (pintype "passive"))
    )
    (net (code "15") (name "Net-(DD1C-VrefHIB)") (class "Default")
      (node (ref "C56") (pin "2") (pinfunction "2_2") (pintype "passive"))
      (node (ref "C60") (pin "2") (pinfunction "2_2") (pintype "passive"))
      (node (ref "DD1") (pin "53") (pinfunction "VrefHIB_53") (pintype "power_in"))
      (node (ref "DD1") (pin "55") (pinfunction "VrefHID_55") (pintype "power_in"))
      (node (ref "R60") (pin "1") (pinfunction "1_1") (pintype "passive"))
    )
    (net (code "16") (name "Net-(DD1C-X1)") (class "Default")
      (node (ref "C63") (pin "2") (pinfunction "2_2") (pintype "passive"))
      (node (ref "DD1") (pin "123") (pinfunction "X1_123") (pintype "passive"))
      (node (ref "Z1") (pin "1") (pinfunction "1_1") (pintype "passive"))
    )
    (net (code "17") (name "Net-(DD1C-X2)") (class "Default")
      (node (ref "C64") (pin "2") (pinfunction "2_2") (pintype "passive"))
      (node (ref "DD1") (pin "121") (pinfunction "X2_121") (pintype "passive"))
      (node (ref "Z1") (pin "2") (pinfunction "2_2") (pintype "passive"))
    )
    (net (code "18") (name "Net-(DD4-BST)") (class "Default")
      (node (ref "C68") (pin "2") (pinfunction "2_2") (pintype "passive"))
      (node (ref "DD4") (pin "1") (pinfunction "BST_1") (pintype "passive"))
    )
    (net (code "19") (name "Net-(DD4-CTRL)") (class "Default")
      (node (ref "DD4") (pin "5") (pinfunction "CTRL_5") (pintype "passive"))
      (node (ref "R61") (pin "1") (pinfunction "1_1") (pintype "passive"))
      (node (ref "R62") (pin "2") (pinfunction "2_2") (pintype "passive"))
    )
    (net (code "20") (name "Net-(DD4-LX)") (class "Default")
      (node (ref "C68") (pin "1") (pinfunction "1_1") (pintype "passive"))
      (node (ref "DD4") (pin "8") (pinfunction "LX_8") (pintype "passive"))
      (node (ref "L7") (pin "2") (pinfunction "2_2") (pintype "passive"))
      (node (ref "VD7") (pin "2") (pinfunction "2_2") (pintype "passive"))
    )
    (net (code "21") (name "Net-(DD4-VD)") (class "Default")
      (node (ref "C69") (pin "2") (pinfunction "2_2") (pintype "passive"))
      (node (ref "DD4") (pin "2") (pinfunction "VD_2") (pintype "passive"))
    )
    (net (code "22") (name "Net-(DD5-FB)") (class "Default")
      (node (ref "DD5") (pin "4") (pinfunction "FB_4") (pintype "passive"))
      (node (ref "R63") (pin "2") (pinfunction "2_2") (pintype "passive"))
      (node (ref "R64") (pin "2") (pinfunction "2_2") (pintype "passive"))
    )
    (net (code "23") (name "Net-(DD5-PG)") (class "Default")
      (node (ref "DD5") (pin "6") (pinfunction "PG_6") (pintype "passive"))
      (node (ref "R65") (pin "2") (pinfunction "2_2") (pintype "passive"))
    )
    (net (code "24") (name "Net-(DD5-SW)") (class "Default")
      (node (ref "DD5") (pin "7") (pinfunction "SW_7") (pintype "passive"))
      (node (ref "L8") (pin "2") (pinfunction "2_2") (pintype "passive"))
    )
    (net (code "25") (name "Net-(L3-Pad2)") (class "Default")
      (node (ref "L3") (pin "2") (pinfunction "2_2") (pintype "passive"))
      (node (ref "R60") (pin "2") (pinfunction "2_2") (pintype "passive"))
    )
    (net (code "26") (name "Net-(L4-Pad2)") (class "Default")
      (node (ref "L4") (pin "2") (pinfunction "2_2") (pintype "passive"))
      (node (ref "R59") (pin "2") (pinfunction "2_2") (pintype "passive"))
    )
    (net (code "27") (name "VDDIO") (class "Default")
      (node (ref "C100") (pin "1") (pinfunction "1_1") (pintype "passive"))
      (node (ref "C102") (pin "2") (pinfunction "2_2") (pintype "passive"))
      (node (ref "C103") (pin "1") (pinfunction "1_1") (pintype "passive"))
      (node (ref "C105") (pin "2") (pinfunction "2_2") (pintype "passive"))
      (node (ref "C106") (pin "1") (pinfunction "1_1") (pintype "passive"))
      (node (ref "C107") (pin "1") (pinfunction "1_1") (pintype "passive"))
      (node (ref "C108") (pin "1") (pinfunction "1_1") (pintype "passive"))
      (node (ref "C51") (pin "2") (pinfunction "2_2") (pintype "passive"))
      (node (ref "C52") (pin "2") (pinfunction "2_2") (pintype "passive"))
      (node (ref "C71") (pin "2") (pinfunction "2_2") (pintype "passive"))
      (node (ref "C72") (pin "1") (pinfunction "1_1") (pintype "passive"))
      (node (ref "C74") (pin "2") (pinfunction "2_2") (pintype "passive"))
      (node (ref "C75") (pin "1") (pinfunction "1_1") (pintype "passive"))
      (node (ref "C77") (pin "2") (pinfunction "2_2") (pintype "passive"))
      (node (ref "C78") (pin "1") (pinfunction "1_1") (pintype "passive"))
      (node (ref "C81") (pin "2") (pinfunction "2_2") (pintype "passive"))
      (node (ref "C82") (pin "1") (pinfunction "1_1") (pintype "passive"))
      (node (ref "C85") (pin "2") (pinfunction "2_2") (pintype "passive"))
      (node (ref "C86") (pin "1") (pinfunction "1_1") (pintype "passive"))
      (node (ref "C89") (pin "2") (pinfunction "2_2") (pintype "passive"))
      (node (ref "C90") (pin "1") (pinfunction "1_1") (pintype "passive"))
      (node (ref "C93") (pin "2") (pinfunction "2_2") (pintype "passive"))
      (node (ref "C94") (pin "1") (pinfunction "1_1") (pintype "passive"))
      (node (ref "C96") (pin "2") (pinfunction "2_2") (pintype "passive"))
      (node (ref "C97") (pin "1") (pinfunction "1_1") (pintype "passive"))
      (node (ref "C99") (pin "2") (pinfunction "2_2") (pintype "passive"))
      (node (ref "DD1") (pin "106") (pinfunction "VDDIO_106") (pintype "power_in"))
      (node (ref "DD1") (pin "11") (pinfunction "VDDIO_11") (pintype "power_in"))
      (node (ref "DD1") (pin "114") (pinfunction "VDDIO_114") (pintype "power_in"))
      (node (ref "DD1") (pin "116") (pinfunction "VDDIO_116") (pintype "power_in"))
      (node (ref "DD1") (pin "119") (pinfunction "VREGENZ_119") (pintype "power_in"))
      (node (ref "DD1") (pin "127") (pinfunction "VDDIO_127") (pintype "power_in"))
      (node (ref "DD1") (pin "138") (pinfunction "VDDIO_138") (pintype "power_in"))
      (node (ref "DD1") (pin "147") (pinfunction "VDDIO_147") (pintype "power_in"))
      (node (ref "DD1") (pin "15") (pinfunction "VDDIO_15") (pintype "power_in"))
      (node (ref "DD1") (pin "152") (pinfunction "VDDIO_152") (pintype "power_in"))
      (node (ref "DD1") (pin "159") (pinfunction "VDDIO_159") (pintype "power_in"))
      (node (ref "DD1") (pin "168") (pinfunction "VDDIO_168") (pintype "power_in"))
      (node (ref "DD1") (pin "20") (pinfunction "VDDIO_20") (pintype "power_in"))
      (node (ref "DD1") (pin "26") (pinfunction "VDDIO_26") (pintype "power_in"))
      (node (ref "DD1") (pin "3") (pinfunction "VDDIO_3") (pintype "power_in"))
      (node (ref "DD1") (pin "62") (pinfunction "VDDIO_62") (pintype "power_in"))
      (node (ref "DD1") (pin "68") (pinfunction "VDDIO_68") (pintype "power_in"))
      (node (ref "DD1") (pin "72") (pinfunction "VDD3V3FL_72") (pintype "power_in"))
      (node (ref "DD1") (pin "75") (pinfunction "VDDIO_75") (pintype "power_in"))
      (node (ref "DD1") (pin "82") (pinfunction "VDDIO_82") (pintype "power_in"))
      (node (ref "DD1") (pin "88") (pinfunction "VDDIO_88") (pintype "power_in"))
      (node (ref "DD1") (pin "91") (pinfunction "VDDIO_91") (pintype "power_in"))
      (node (ref "DD1") (pin "99") (pinfunction "VDDIO_99") (pintype "power_in"))
      (node (ref "L10") (pin "1") (pinfunction "1_1") (pintype "passive"))
      (node (ref "L3") (pin "1") (pinfunction "1_1") (pintype "passive"))
      (node (ref "L4") (pin "1") (pinfunction "1_1") (pintype "passive"))
      (node (ref "L5") (pin "1") (pinfunction "1_1") (pintype "passive"))
      (node (ref "L6") (pin "1") (pinfunction "1_1") (pintype "passive"))
    )
    (net (code "28") (name "unconnected-(DD1C-ERR_RST-Pad92)") (class "Default")
      (node (ref "DD1") (pin "92") (pinfunction "ERR_RST_92") (pintype "power_in"))
    )
    (net (code "29") (name "unconnected-(DD1C-FLT1-Pad73)") (class "Default")
      (node (ref "DD1") (pin "73") (pinfunction "FLT1_73") (pintype "power_in"))
    )
    (net (code "30") (name "unconnected-(DD1C-FLT2-Pad74)") (class "Default")
      (node (ref "DD1") (pin "74") (pinfunction "FLT2_74") (pintype "power_in"))
    )
  )
)
